# Bluetooth.net
KiCad netlist of a schematic drawn in Altium Designer
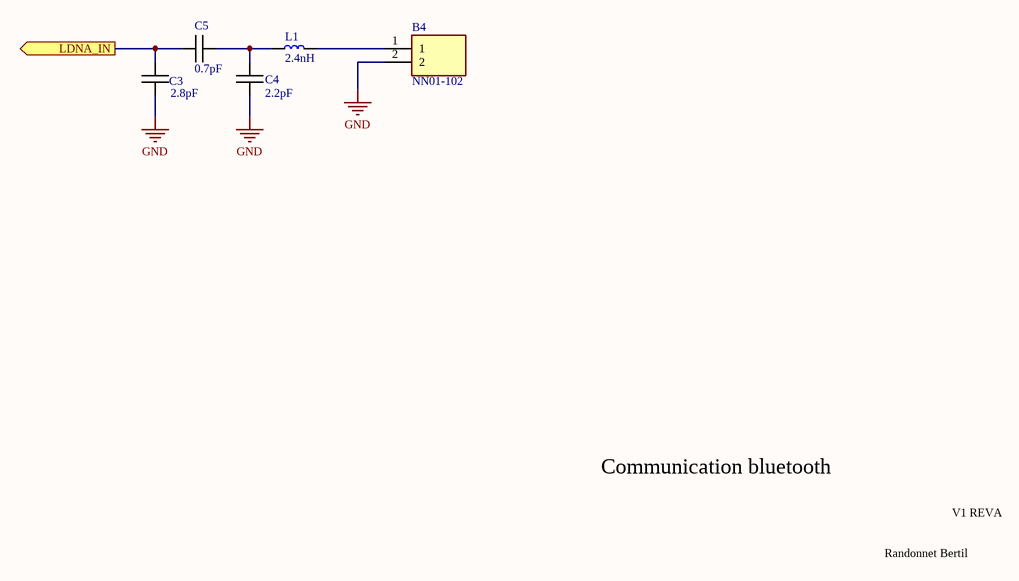
[diagram p0: Bluetooth.SchDoc]

(export (version "E")
  (design (tool "Eeschema 10.0.6"))
  (components
    (comp (ref "B4")
      (value "NN01-102")
      (footprint "NN01-102")
      (description "Antennes Compact Reach Xtend 2.4 GHz")
      (libsource (lib "SCHLibrary") (part "NN01-102"))
    )
    (comp (ref "C3")
      (value "2.8pF")
      (footprint "CAPC1005X06N")
      (libsource (lib "SCHLibrary") (part "Capacitor"))
    )
    (comp (ref "C4")
      (value "2.2pF")
      (footprint "CAPC1005X06N")
      (libsource (lib "SCHLibrary") (part "Capacitor"))
    )
    (comp (ref "C5")
      (value "0.7pF")
      (footprint "CAPC1005X06N")
      (libsource (lib "SCHLibrary") (part "Capacitor"))
    )
    (comp (ref "L1")
      (value "2.4nH")
      (footprint "LQPC1005X06N")
      (libsource (lib "SCHLibrary") (part "Bobine"))
    )
  )
  (nets
    (net (code "1") (name "/LDNA_IN") (class "Default")
      (node (ref "C3") (pin "1") (pinfunction "1_1") (pintype "passive"))
      (node (ref "C5") (pin "1") (pinfunction "1_1") (pintype "passive"))
    )
    (net (code "2") (name "GND") (class "Default")
      (node (ref "B4") (pin "2") (pinfunction "2_2") (pintype "passive"))
      (node (ref "C3") (pin "2") (pinfunction "2_2") (pintype "passive"))
      (node (ref "C4") (pin "2") (pinfunction "2_2") (pintype "passive"))
    )
    (net (code "3") (name "Net-(B4-Pad1)") (class "Default")
      (node (ref "B4") (pin "1") (pinfunction "1_1") (pintype "passive"))
      (node (ref "L1") (pin "2") (pinfunction "2_2") (pintype "passive"))
    )
    (net (code "4") (name "Net-(C4-Pad1)") (class "Default")
      (node (ref "C4") (pin "1") (pinfunction "1_1") (pintype "passive"))
      (node (ref "C5") (pin "2") (pinfunction "2_2") (pintype "passive"))
      (node (ref "L1") (pin "1") (pinfunction "1_1") (pintype "passive"))
    )
  )
)
